# TOP.net
KiCad netlist of a schematic drawn in Altium Designer
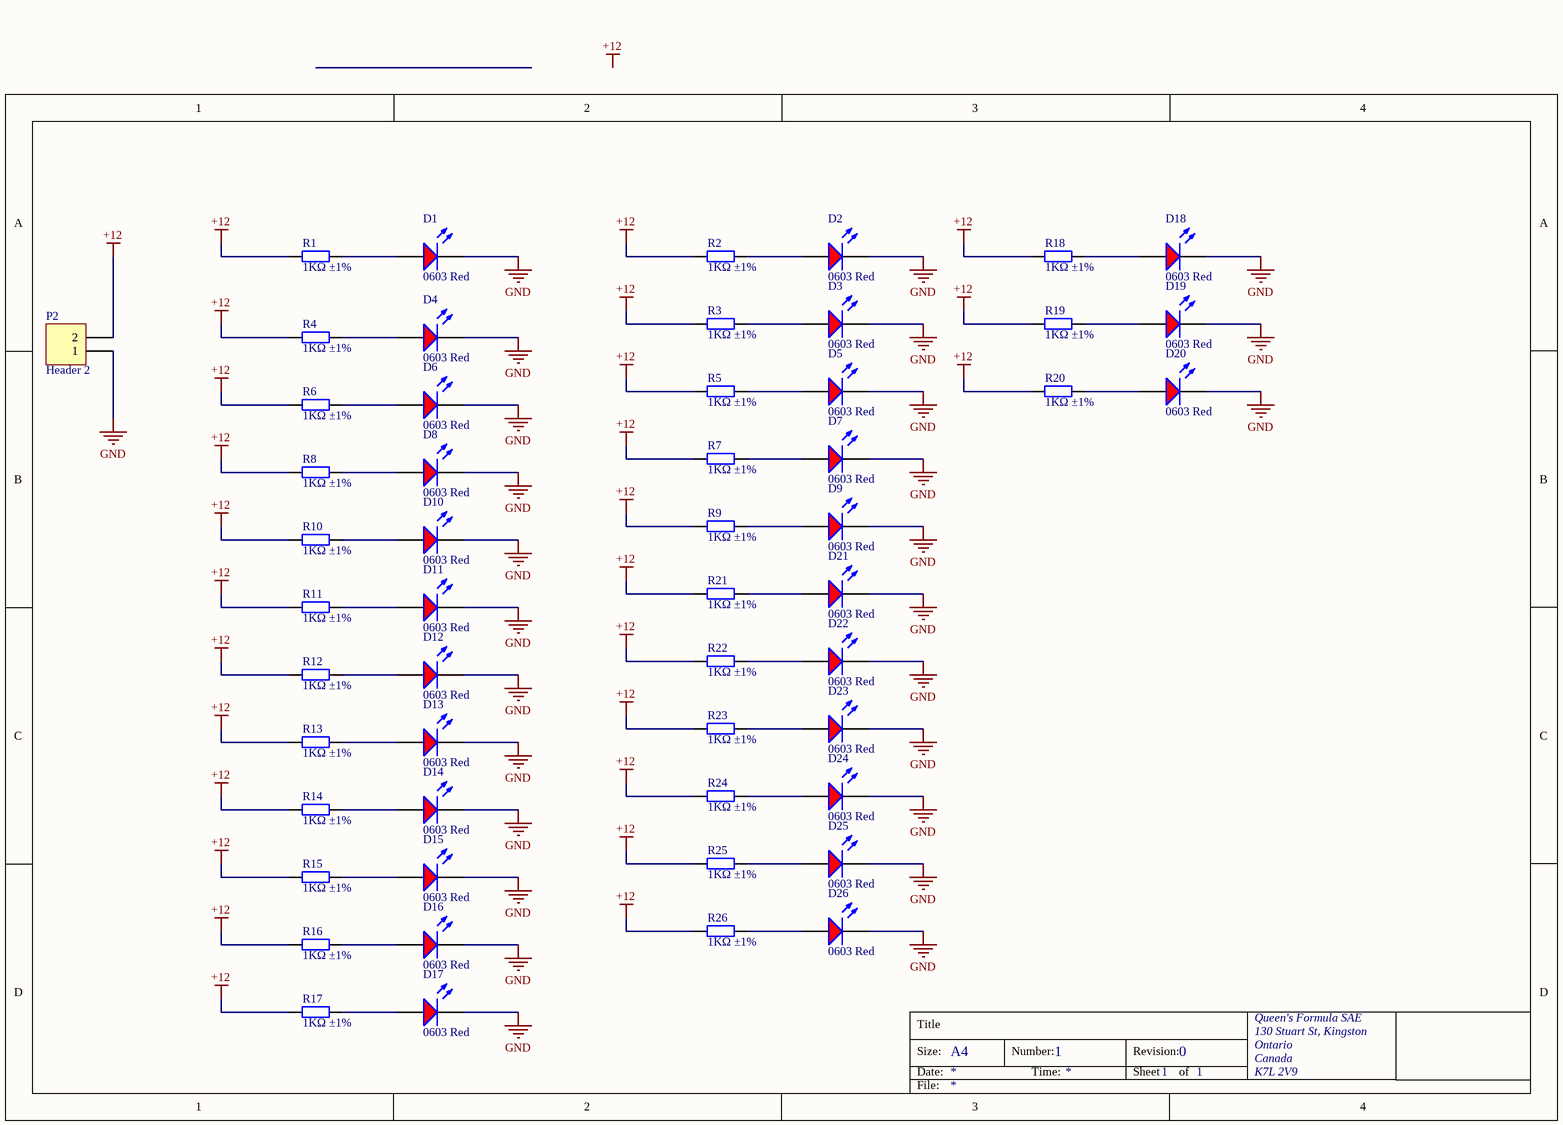
[diagram p0: TOP.SchDoc]

(export (version "E")
  (design (tool "Eeschema 10.0.6"))
  (components
    (comp (ref "D1")
      (value "0603 Red")
      (footprint "0603_LED_S1")
      (description "LED")
      (libsource (lib "LED") (part "0603 LED Red"))
    )
    (comp (ref "D2")
      (value "0603 Red")
      (footprint "0603_LED_S1")
      (description "LED")
      (libsource (lib "LED") (part "0603 LED Red"))
    )
    (comp (ref "D3")
      (value "0603 Red")
      (footprint "0603_LED_S1")
      (description "LED")
      (libsource (lib "LED") (part "0603 LED Red"))
    )
    (comp (ref "D4")
      (value "0603 Red")
      (footprint "0603_LED_S1")
      (description "LED")
      (libsource (lib "LED") (part "0603 LED Red"))
    )
    (comp (ref "D5")
      (value "0603 Red")
      (footprint "0603_LED_S1")
      (description "LED")
      (libsource (lib "LED") (part "0603 LED Red"))
    )
    (comp (ref "D6")
      (value "0603 Red")
      (footprint "0603_LED_S1")
      (description "LED")
      (libsource (lib "LED") (part "0603 LED Red"))
    )
    (comp (ref "D7")
      (value "0603 Red")
      (footprint "0603_LED_S1")
      (description "LED")
      (libsource (lib "LED") (part "0603 LED Red"))
    )
    (comp (ref "D8")
      (value "0603 Red")
      (footprint "0603_LED_S1")
      (description "LED")
      (libsource (lib "LED") (part "0603 LED Red"))
    )
    (comp (ref "D9")
      (value "0603 Red")
      (footprint "0603_LED_S1")
      (description "LED")
      (libsource (lib "LED") (part "0603 LED Red"))
    )
    (comp (ref "D10")
      (value "0603 Red")
      (footprint "0603_LED_S1")
      (description "LED")
      (libsource (lib "LED") (part "0603 LED Red"))
    )
    (comp (ref "D11")
      (value "0603 Red")
      (footprint "0603_LED_S1")
      (description "LED")
      (libsource (lib "LED") (part "0603 LED Red"))
    )
    (comp (ref "D12")
      (value "0603 Red")
      (footprint "0603_LED_S1")
      (description "LED")
      (libsource (lib "LED") (part "0603 LED Red"))
    )
    (comp (ref "D13")
      (value "0603 Red")
      (footprint "0603_LED_S1")
      (description "LED")
      (libsource (lib "LED") (part "0603 LED Red"))
    )
    (comp (ref "D14")
      (value "0603 Red")
      (footprint "0603_LED_S1")
      (description "LED")
      (libsource (lib "LED") (part "0603 LED Red"))
    )
    (comp (ref "D15")
      (value "0603 Red")
      (footprint "0603_LED_S1")
      (description "LED")
      (libsource (lib "LED") (part "0603 LED Red"))
    )
    (comp (ref "D16")
      (value "0603 Red")
      (footprint "0603_LED_S1")
      (description "LED")
      (libsource (lib "LED") (part "0603 LED Red"))
    )
    (comp (ref "D17")
      (value "0603 Red")
      (footprint "0603_LED_S1")
      (description "LED")
      (libsource (lib "LED") (part "0603 LED Red"))
    )
    (comp (ref "D18")
      (value "0603 Red")
      (footprint "0603_LED_S1")
      (description "LED")
      (libsource (lib "LED") (part "0603 LED Red"))
    )
    (comp (ref "D19")
      (value "0603 Red")
      (footprint "0603_LED_S1")
      (description "LED")
      (libsource (lib "LED") (part "0603 LED Red"))
    )
    (comp (ref "D20")
      (value "0603 Red")
      (footprint "0603_LED_S1")
      (description "LED")
      (libsource (lib "LED") (part "0603 LED Red"))
    )
    (comp (ref "D21")
      (value "0603 Red")
      (footprint "0603_LED_S1")
      (description "LED")
      (libsource (lib "LED") (part "0603 LED Red"))
    )
    (comp (ref "D22")
      (value "0603 Red")
      (footprint "0603_LED_S1")
      (description "LED")
      (libsource (lib "LED") (part "0603 LED Red"))
    )
    (comp (ref "D23")
      (value "0603 Red")
      (footprint "0603_LED_S1")
      (description "LED")
      (libsource (lib "LED") (part "0603 LED Red"))
    )
    (comp (ref "D24")
      (value "0603 Red")
      (footprint "0603_LED_S1")
      (description "LED")
      (libsource (lib "LED") (part "0603 LED Red"))
    )
    (comp (ref "D25")
      (value "0603 Red")
      (footprint "0603_LED_S1")
      (description "LED")
      (libsource (lib "LED") (part "0603 LED Red"))
    )
    (comp (ref "D26")
      (value "0603 Red")
      (footprint "0603_LED_S1")
      (description "LED")
      (libsource (lib "LED") (part "0603 LED Red"))
    )
    (comp (ref "P2")
      (value "Header 2")
      (footprint "HDR1X2")
      (description "Header, 2-Pin")
      (fields (field (name "PUBLISHER") "Altium Limited"))
      (libsource (lib "Miscellaneous Connectors") (part "Header 2"))
    )
    (comp (ref "R1")
      (value "1KΩ ±1%")
      (footprint "0603_R")
      (description "Chip resistor")
      (fields (field (name "MANUFACTURER") "Uniroyal Elec") (field (name "PARTNUMBER") "0603WAF1001T5E"))
      (libsource (lib "RES") (part "0603 1K (1001) 1%"))
    )
    (comp (ref "R2")
      (value "1KΩ ±1%")
      (footprint "0603_R")
      (description "Chip resistor")
      (fields (field (name "MANUFACTURER") "Uniroyal Elec") (field (name "PARTNUMBER") "0603WAF1001T5E"))
      (libsource (lib "RES") (part "0603 1K (1001) 1%"))
    )
    (comp (ref "R3")
      (value "1KΩ ±1%")
      (footprint "0603_R")
      (description "Chip resistor")
      (fields (field (name "MANUFACTURER") "Uniroyal Elec") (field (name "PARTNUMBER") "0603WAF1001T5E"))
      (libsource (lib "RES") (part "0603 1K (1001) 1%"))
    )
    (comp (ref "R4")
      (value "1KΩ ±1%")
      (footprint "0603_R")
      (description "Chip resistor")
      (fields (field (name "MANUFACTURER") "Uniroyal Elec") (field (name "PARTNUMBER") "0603WAF1001T5E"))
      (libsource (lib "RES") (part "0603 1K (1001) 1%"))
    )
    (comp (ref "R5")
      (value "1KΩ ±1%")
      (footprint "0603_R")
      (description "Chip resistor")
      (fields (field (name "MANUFACTURER") "Uniroyal Elec") (field (name "PARTNUMBER") "0603WAF1001T5E"))
      (libsource (lib "RES") (part "0603 1K (1001) 1%"))
    )
    (comp (ref "R6")
      (value "1KΩ ±1%")
      (footprint "0603_R")
      (description "Chip resistor")
      (fields (field (name "MANUFACTURER") "Uniroyal Elec") (field (name "PARTNUMBER") "0603WAF1001T5E"))
      (libsource (lib "RES") (part "0603 1K (1001) 1%"))
    )
    (comp (ref "R7")
      (value "1KΩ ±1%")
      (footprint "0603_R")
      (description "Chip resistor")
      (fields (field (name "MANUFACTURER") "Uniroyal Elec") (field (name "PARTNUMBER") "0603WAF1001T5E"))
      (libsource (lib "RES") (part "0603 1K (1001) 1%"))
    )
    (comp (ref "R8")
      (value "1KΩ ±1%")
      (footprint "0603_R")
      (description "Chip resistor")
      (fields (field (name "MANUFACTURER") "Uniroyal Elec") (field (name "PARTNUMBER") "0603WAF1001T5E"))
      (libsource (lib "RES") (part "0603 1K (1001) 1%"))
    )
    (comp (ref "R9")
      (value "1KΩ ±1%")
      (footprint "0603_R")
      (description "Chip resistor")
      (fields (field (name "MANUFACTURER") "Uniroyal Elec") (field (name "PARTNUMBER") "0603WAF1001T5E"))
      (libsource (lib "RES") (part "0603 1K (1001) 1%"))
    )
    (comp (ref "R10")
      (value "1KΩ ±1%")
      (footprint "0603_R")
      (description "Chip resistor")
      (fields (field (name "MANUFACTURER") "Uniroyal Elec") (field (name "PARTNUMBER") "0603WAF1001T5E"))
      (libsource (lib "RES") (part "0603 1K (1001) 1%"))
    )
    (comp (ref "R11")
      (value "1KΩ ±1%")
      (footprint "0603_R")
      (description "Chip resistor")
      (fields (field (name "MANUFACTURER") "Uniroyal Elec") (field (name "PARTNUMBER") "0603WAF1001T5E"))
      (libsource (lib "RES") (part "0603 1K (1001) 1%"))
    )
    (comp (ref "R12")
      (value "1KΩ ±1%")
      (footprint "0603_R")
      (description "Chip resistor")
      (fields (field (name "MANUFACTURER") "Uniroyal Elec") (field (name "PARTNUMBER") "0603WAF1001T5E"))
      (libsource (lib "RES") (part "0603 1K (1001) 1%"))
    )
    (comp (ref "R13")
      (value "1KΩ ±1%")
      (footprint "0603_R")
      (description "Chip resistor")
      (fields (field (name "MANUFACTURER") "Uniroyal Elec") (field (name "PARTNUMBER") "0603WAF1001T5E"))
      (libsource (lib "RES") (part "0603 1K (1001) 1%"))
    )
    (comp (ref "R14")
      (value "1KΩ ±1%")
      (footprint "0603_R")
      (description "Chip resistor")
      (fields (field (name "MANUFACTURER") "Uniroyal Elec") (field (name "PARTNUMBER") "0603WAF1001T5E"))
      (libsource (lib "RES") (part "0603 1K (1001) 1%"))
    )
    (comp (ref "R15")
      (value "1KΩ ±1%")
      (footprint "0603_R")
      (description "Chip resistor")
      (fields (field (name "MANUFACTURER") "Uniroyal Elec") (field (name "PARTNUMBER") "0603WAF1001T5E"))
      (libsource (lib "RES") (part "0603 1K (1001) 1%"))
    )
    (comp (ref "R16")
      (value "1KΩ ±1%")
      (footprint "0603_R")
      (description "Chip resistor")
      (fields (field (name "MANUFACTURER") "Uniroyal Elec") (field (name "PARTNUMBER") "0603WAF1001T5E"))
      (libsource (lib "RES") (part "0603 1K (1001) 1%"))
    )
    (comp (ref "R17")
      (value "1KΩ ±1%")
      (footprint "0603_R")
      (description "Chip resistor")
      (fields (field (name "MANUFACTURER") "Uniroyal Elec") (field (name "PARTNUMBER") "0603WAF1001T5E"))
      (libsource (lib "RES") (part "0603 1K (1001) 1%"))
    )
    (comp (ref "R18")
      (value "1KΩ ±1%")
      (footprint "0603_R")
      (description "Chip resistor")
      (fields (field (name "MANUFACTURER") "Uniroyal Elec") (field (name "PARTNUMBER") "0603WAF1001T5E"))
      (libsource (lib "RES") (part "0603 1K (1001) 1%"))
    )
    (comp (ref "R19")
      (value "1KΩ ±1%")
      (footprint "0603_R")
      (description "Chip resistor")
      (fields (field (name "MANUFACTURER") "Uniroyal Elec") (field (name "PARTNUMBER") "0603WAF1001T5E"))
      (libsource (lib "RES") (part "0603 1K (1001) 1%"))
    )
    (comp (ref "R20")
      (value "1KΩ ±1%")
      (footprint "0603_R")
      (description "Chip resistor")
      (fields (field (name "MANUFACTURER") "Uniroyal Elec") (field (name "PARTNUMBER") "0603WAF1001T5E"))
      (libsource (lib "RES") (part "0603 1K (1001) 1%"))
    )
    (comp (ref "R21")
      (value "1KΩ ±1%")
      (footprint "0603_R")
      (description "Chip resistor")
      (fields (field (name "MANUFACTURER") "Uniroyal Elec") (field (name "PARTNUMBER") "0603WAF1001T5E"))
      (libsource (lib "RES") (part "0603 1K (1001) 1%"))
    )
    (comp (ref "R22")
      (value "1KΩ ±1%")
      (footprint "0603_R")
      (description "Chip resistor")
      (fields (field (name "MANUFACTURER") "Uniroyal Elec") (field (name "PARTNUMBER") "0603WAF1001T5E"))
      (libsource (lib "RES") (part "0603 1K (1001) 1%"))
    )
    (comp (ref "R23")
      (value "1KΩ ±1%")
      (footprint "0603_R")
      (description "Chip resistor")
      (fields (field (name "MANUFACTURER") "Uniroyal Elec") (field (name "PARTNUMBER") "0603WAF1001T5E"))
      (libsource (lib "RES") (part "0603 1K (1001) 1%"))
    )
    (comp (ref "R24")
      (value "1KΩ ±1%")
      (footprint "0603_R")
      (description "Chip resistor")
      (fields (field (name "MANUFACTURER") "Uniroyal Elec") (field (name "PARTNUMBER") "0603WAF1001T5E"))
      (libsource (lib "RES") (part "0603 1K (1001) 1%"))
    )
    (comp (ref "R25")
      (value "1KΩ ±1%")
      (footprint "0603_R")
      (description "Chip resistor")
      (fields (field (name "MANUFACTURER") "Uniroyal Elec") (field (name "PARTNUMBER") "0603WAF1001T5E"))
      (libsource (lib "RES") (part "0603 1K (1001) 1%"))
    )
    (comp (ref "R26")
      (value "1KΩ ±1%")
      (footprint "0603_R")
      (description "Chip resistor")
      (fields (field (name "MANUFACTURER") "Uniroyal Elec") (field (name "PARTNUMBER") "0603WAF1001T5E"))
      (libsource (lib "RES") (part "0603 1K (1001) 1%"))
    )
  )
  (nets
    (net (code "1") (name "+12") (class "Default")
      (node (ref "P2") (pin "2") (pinfunction "2_2") (pintype "passive"))
      (node (ref "R1") (pin "1") (pinfunction "1_1") (pintype "passive"))
      (node (ref "R10") (pin "1") (pinfunction "1_1") (pintype "passive"))
      (node (ref "R11") (pin "1") (pinfunction "1_1") (pintype "passive"))
      (node (ref "R12") (pin "1") (pinfunction "1_1") (pintype "passive"))
      (node (ref "R13") (pin "1") (pinfunction "1_1") (pintype "passive"))
      (node (ref "R14") (pin "1") (pinfunction "1_1") (pintype "passive"))
      (node (ref "R15") (pin "1") (pinfunction "1_1") (pintype "passive"))
      (node (ref "R16") (pin "1") (pinfunction "1_1") (pintype "passive"))
      (node (ref "R17") (pin "1") (pinfunction "1_1") (pintype "passive"))
      (node (ref "R18") (pin "1") (pinfunction "1_1") (pintype "passive"))
      (node (ref "R19") (pin "1") (pinfunction "1_1") (pintype "passive"))
      (node (ref "R2") (pin "1") (pinfunction "1_1") (pintype "passive"))
      (node (ref "R20") (pin "1") (pinfunction "1_1") (pintype "passive"))
      (node (ref "R21") (pin "1") (pinfunction "1_1") (pintype "passive"))
      (node (ref "R22") (pin "1") (pinfunction "1_1") (pintype "passive"))
      (node (ref "R23") (pin "1") (pinfunction "1_1") (pintype "passive"))
      (node (ref "R24") (pin "1") (pinfunction "1_1") (pintype "passive"))
      (node (ref "R25") (pin "1") (pinfunction "1_1") (pintype "passive"))
      (node (ref "R26") (pin "1") (pinfunction "1_1") (pintype "passive"))
      (node (ref "R3") (pin "1") (pinfunction "1_1") (pintype "passive"))
      (node (ref "R4") (pin "1") (pinfunction "1_1") (pintype "passive"))
      (node (ref "R5") (pin "1") (pinfunction "1_1") (pintype "passive"))
      (node (ref "R6") (pin "1") (pinfunction "1_1") (pintype "passive"))
      (node (ref "R7") (pin "1") (pinfunction "1_1") (pintype "passive"))
      (node (ref "R8") (pin "1") (pinfunction "1_1") (pintype "passive"))
      (node (ref "R9") (pin "1") (pinfunction "1_1") (pintype "passive"))
    )
    (net (code "2") (name "GND") (class "Default")
      (node (ref "D1") (pin "K") (pinfunction "K_K") (pintype "passive"))
      (node (ref "D10") (pin "K") (pinfunction "K_K") (pintype "passive"))
      (node (ref "D11") (pin "K") (pinfunction "K_K") (pintype "passive"))
      (node (ref "D12") (pin "K") (pinfunction "K_K") (pintype "passive"))
      (node (ref "D13") (pin "K") (pinfunction "K_K") (pintype "passive"))
      (node (ref "D14") (pin "K") (pinfunction "K_K") (pintype "passive"))
      (node (ref "D15") (pin "K") (pinfunction "K_K") (pintype "passive"))
      (node (ref "D16") (pin "K") (pinfunction "K_K") (pintype "passive"))
      (node (ref "D17") (pin "K") (pinfunction "K_K") (pintype "passive"))
      (node (ref "D18") (pin "K") (pinfunction "K_K") (pintype "passive"))
      (node (ref "D19") (pin "K") (pinfunction "K_K") (pintype "passive"))
      (node (ref "D2") (pin "K") (pinfunction "K_K") (pintype "passive"))
      (node (ref "D20") (pin "K") (pinfunction "K_K") (pintype "passive"))
      (node (ref "D21") (pin "K") (pinfunction "K_K") (pintype "passive"))
      (node (ref "D22") (pin "K") (pinfunction "K_K") (pintype "passive"))
      (node (ref "D23") (pin "K") (pinfunction "K_K") (pintype "passive"))
      (node (ref "D24") (pin "K") (pinfunction "K_K") (pintype "passive"))
      (node (ref "D25") (pin "K") (pinfunction "K_K") (pintype "passive"))
      (node (ref "D26") (pin "K") (pinfunction "K_K") (pintype "passive"))
      (node (ref "D3") (pin "K") (pinfunction "K_K") (pintype "passive"))
      (node (ref "D4") (pin "K") (pinfunction "K_K") (pintype "passive"))
      (node (ref "D5") (pin "K") (pinfunction "K_K") (pintype "passive"))
      (node (ref "D6") (pin "K") (pinfunction "K_K") (pintype "passive"))
      (node (ref "D7") (pin "K") (pinfunction "K_K") (pintype "passive"))
      (node (ref "D8") (pin "K") (pinfunction "K_K") (pintype "passive"))
      (node (ref "D9") (pin "K") (pinfunction "K_K") (pintype "passive"))
      (node (ref "P2") (pin "1") (pinfunction "1_1") (pintype "passive"))
    )
    (net (code "3") (name "Net-(D1-PadA)") (class "Default")
      (node (ref "D1") (pin "A") (pinfunction "A_A") (pintype "passive"))
      (node (ref "R1") (pin "2") (pinfunction "2_2") (pintype "passive"))
    )
    (net (code "4") (name "Net-(D2-PadA)") (class "Default")
      (node (ref "D2") (pin "A") (pinfunction "A_A") (pintype "passive"))
      (node (ref "R2") (pin "2") (pinfunction "2_2") (pintype "passive"))
    )
    (net (code "5") (name "Net-(D3-PadA)") (class "Default")
      (node (ref "D3") (pin "A") (pinfunction "A_A") (pintype "passive"))
      (node (ref "R3") (pin "2") (pinfunction "2_2") (pintype "passive"))
    )
    (net (code "6") (name "Net-(D4-PadA)") (class "Default")
      (node (ref "D4") (pin "A") (pinfunction "A_A") (pintype "passive"))
      (node (ref "R4") (pin "2") (pinfunction "2_2") (pintype "passive"))
    )
    (net (code "7") (name "Net-(D5-PadA)") (class "Default")
      (node (ref "D5") (pin "A") (pinfunction "A_A") (pintype "passive"))
      (node (ref "R5") (pin "2") (pinfunction "2_2") (pintype "passive"))
    )
    (net (code "8") (name "Net-(D6-PadA)") (class "Default")
      (node (ref "D6") (pin "A") (pinfunction "A_A") (pintype "passive"))
      (node (ref "R6") (pin "2") (pinfunction "2_2") (pintype "passive"))
    )
    (net (code "9") (name "Net-(D7-PadA)") (class "Default")
      (node (ref "D7") (pin "A") (pinfunction "A_A") (pintype "passive"))
      (node (ref "R7") (pin "2") (pinfunction "2_2") (pintype "passive"))
    )
    (net (code "10") (name "Net-(D8-PadA)") (class "Default")
      (node (ref "D8") (pin "A") (pinfunction "A_A") (pintype "passive"))
      (node (ref "R8") (pin "2") (pinfunction "2_2") (pintype "passive"))
    )
    (net (code "11") (name "Net-(D9-PadA)") (class "Default")
      (node (ref "D9") (pin "A") (pinfunction "A_A") (pintype "passive"))
      (node (ref "R9") (pin "2") (pinfunction "2_2") (pintype "passive"))
    )
    (net (code "12") (name "Net-(D10-PadA)") (class "Default")
      (node (ref "D10") (pin "A") (pinfunction "A_A") (pintype "passive"))
      (node (ref "R10") (pin "2") (pinfunction "2_2") (pintype "passive"))
    )
    (net (code "13") (name "Net-(D11-PadA)") (class "Default")
      (node (ref "D11") (pin "A") (pinfunction "A_A") (pintype "passive"))
      (node (ref "R11") (pin "2") (pinfunction "2_2") (pintype "passive"))
    )
    (net (code "14") (name "Net-(D12-PadA)") (class "Default")
      (node (ref "D12") (pin "A") (pinfunction "A_A") (pintype "passive"))
      (node (ref "R12") (pin "2") (pinfunction "2_2") (pintype "passive"))
    )
    (net (code "15") (name "Net-(D13-PadA)") (class "Default")
      (node (ref "D13") (pin "A") (pinfunction "A_A") (pintype "passive"))
      (node (ref "R13") (pin "2") (pinfunction "2_2") (pintype "passive"))
    )
    (net (code "16") (name "Net-(D14-PadA)") (class "Default")
      (node (ref "D14") (pin "A") (pinfunction "A_A") (pintype "passive"))
      (node (ref "R14") (pin "2") (pinfunction "2_2") (pintype "passive"))
    )
    (net (code "17") (name "Net-(D15-PadA)") (class "Default")
      (node (ref "D15") (pin "A") (pinfunction "A_A") (pintype "passive"))
      (node (ref "R15") (pin "2") (pinfunction "2_2") (pintype "passive"))
    )
    (net (code "18") (name "Net-(D16-PadA)") (class "Default")
      (node (ref "D16") (pin "A") (pinfunction "A_A") (pintype "passive"))
      (node (ref "R16") (pin "2") (pinfunction "2_2") (pintype "passive"))
    )
    (net (code "19") (name "Net-(D17-PadA)") (class "Default")
      (node (ref "D17") (pin "A") (pinfunction "A_A") (pintype "passive"))
      (node (ref "R17") (pin "2") (pinfunction "2_2") (pintype "passive"))
    )
    (net (code "20") (name "Net-(D18-PadA)") (class "Default")
      (node (ref "D18") (pin "A") (pinfunction "A_A") (pintype "passive"))
      (node (ref "R18") (pin "2") (pinfunction "2_2") (pintype "passive"))
    )
    (net (code "21") (name "Net-(D19-PadA)") (class "Default")
      (node (ref "D19") (pin "A") (pinfunction "A_A") (pintype "passive"))
      (node (ref "R19") (pin "2") (pinfunction "2_2") (pintype "passive"))
    )
    (net (code "22") (name "Net-(D20-PadA)") (class "Default")
      (node (ref "D20") (pin "A") (pinfunction "A_A") (pintype "passive"))
      (node (ref "R20") (pin "2") (pinfunction "2_2") (pintype "passive"))
    )
    (net (code "23") (name "Net-(D21-PadA)") (class "Default")
      (node (ref "D21") (pin "A") (pinfunction "A_A") (pintype "passive"))
      (node (ref "R21") (pin "2") (pinfunction "2_2") (pintype "passive"))
    )
    (net (code "24") (name "Net-(D22-PadA)") (class "Default")
      (node (ref "D22") (pin "A") (pinfunction "A_A") (pintype "passive"))
      (node (ref "R22") (pin "2") (pinfunction "2_2") (pintype "passive"))
    )
    (net (code "25") (name "Net-(D23-PadA)") (class "Default")
      (node (ref "D23") (pin "A") (pinfunction "A_A") (pintype "passive"))
      (node (ref "R23") (pin "2") (pinfunction "2_2") (pintype "passive"))
    )
    (net (code "26") (name "Net-(D24-PadA)") (class "Default")
      (node (ref "D24") (pin "A") (pinfunction "A_A") (pintype "passive"))
      (node (ref "R24") (pin "2") (pinfunction "2_2") (pintype "passive"))
    )
    (net (code "27") (name "Net-(D25-PadA)") (class "Default")
      (node (ref "D25") (pin "A") (pinfunction "A_A") (pintype "passive"))
      (node (ref "R25") (pin "2") (pinfunction "2_2") (pintype "passive"))
    )
    (net (code "28") (name "Net-(D26-PadA)") (class "Default")
      (node (ref "D26") (pin "A") (pinfunction "A_A") (pintype "passive"))
      (node (ref "R26") (pin "2") (pinfunction "2_2") (pintype "passive"))
    )
  )
)
